# AnalogEx_1RedLedFadeInFadeOutUSB.net
KiCad netlist of a schematic drawn in EAGLE
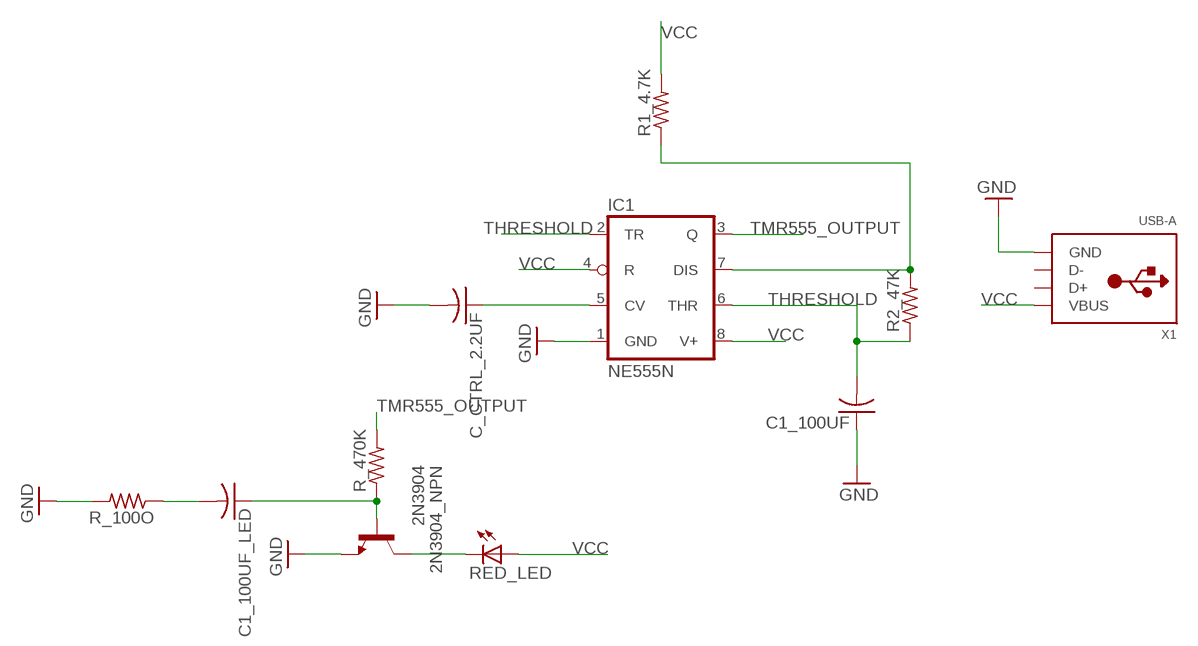
[diagram p0: schematic, sheet 1]

(export (version "E")
  (design (tool "Eeschema 10.0.6"))
  (components
    (comp (ref "2N3904_NPN")
      (value "2N3904")
      (footprint "eagle-import:TO92")
      (libsource (lib "eagle-import") (part "2N3904"))
    )
    (comp (ref "C1_100UF")
      (value "C-US025-030X050")
      (footprint "eagle-import:C025-030X050")
      (libsource (lib "eagle-import") (part "C-US025-030X050"))
    )
    (comp (ref "C1_100UF_LED")
      (value "C-US025-030X050")
      (footprint "eagle-import:C025-030X050")
      (libsource (lib "eagle-import") (part "C-US025-030X050"))
    )
    (comp (ref "C_CTRL_2.2UF")
      (value "C-US025-030X050")
      (footprint "eagle-import:C025-030X050")
      (libsource (lib "eagle-import") (part "C-US025-030X050"))
    )
    (comp (ref "IC1")
      (value "NE555N")
      (footprint "eagle-import:DIL08")
      (libsource (lib "eagle-import") (part "555NNE"))
    )
    (comp (ref "R1_4.7K")
      (value "R-US_0207/10")
      (footprint "eagle-import:0207_10")
      (libsource (lib "eagle-import") (part "R-US_0207/10"))
    )
    (comp (ref "R2_47K")
      (value "R-US_0207/10")
      (footprint "eagle-import:0207_10")
      (libsource (lib "eagle-import") (part "R-US_0207/10"))
    )
    (comp (ref "RED_LED")
      (value "LED5MM")
      (footprint "eagle-import:LED5MM")
      (libsource (lib "eagle-import") (part "LED5MM"))
    )
    (comp (ref "R_100O")
      (value "R-US_0207/10")
      (footprint "eagle-import:0207_10")
      (libsource (lib "eagle-import") (part "R-US_0207/10"))
    )
    (comp (ref "R_470K")
      (value "R-US_0207/10")
      (footprint "eagle-import:0207_10")
      (libsource (lib "eagle-import") (part "R-US_0207/10"))
    )
    (comp (ref "X1")
      (value "USB-A")
      (footprint "eagle-import:MOLEX_480371000")
      (libsource (lib "eagle-import") (part "USB-A"))
    )
  )
  (nets
    (net (code "1") (name "/THRESHOLD") (class "Default")
      (node (ref "C1_100UF") (pin "2") (pinfunction "2_2") (pintype "passive"))
      (node (ref "IC1") (pin "2") (pinfunction "TR_2") (pintype "input"))
      (node (ref "IC1") (pin "6") (pinfunction "THR_6") (pintype "input"))
      (node (ref "R2_47K") (pin "1") (pinfunction "1_1") (pintype "passive"))
    )
    (net (code "2") (name "/TMR555_OUTPUT") (class "Default")
      (node (ref "IC1") (pin "3") (pinfunction "Q_3") (pintype "output"))
      (node (ref "R_470K") (pin "2") (pinfunction "2_2") (pintype "passive"))
    )
    (net (code "3") (name "/VCC") (class "Default")
      (node (ref "IC1") (pin "4") (pinfunction "R_4") (pintype "input"))
      (node (ref "IC1") (pin "8") (pinfunction "V+_8") (pintype "power_in"))
      (node (ref "R1_4.7K") (pin "2") (pinfunction "2_2") (pintype "passive"))
      (node (ref "RED_LED") (pin "A") (pinfunction "A_A") (pintype "passive"))
      (node (ref "X1") (pin "1") (pinfunction "VBUS_1") (pintype "power_in"))
    )
    (net (code "4") (name "GND") (class "Default")
      (node (ref "2N3904_NPN") (pin "3") (pinfunction "E_3") (pintype "passive"))
      (node (ref "C1_100UF") (pin "1") (pinfunction "1_1") (pintype "passive"))
      (node (ref "C_CTRL_2.2UF") (pin "2") (pinfunction "2_2") (pintype "passive"))
      (node (ref "IC1") (pin "1") (pinfunction "GND_1") (pintype "power_in"))
      (node (ref "R_100O") (pin "2") (pinfunction "2_2") (pintype "passive"))
      (node (ref "X1") (pin "4") (pinfunction "GND_4") (pintype "power_in"))
    )
    (net (code "5") (name "Net-(2N3904_NPN-B)") (class "Default")
      (node (ref "2N3904_NPN") (pin "2") (pinfunction "B_2") (pintype "passive"))
      (node (ref "C1_100UF_LED") (pin "1") (pinfunction "1_1") (pintype "passive"))
      (node (ref "R_470K") (pin "1") (pinfunction "1_1") (pintype "passive"))
    )
    (net (code "6") (name "Net-(2N3904_NPN-C)") (class "Default")
      (node (ref "2N3904_NPN") (pin "1") (pinfunction "C_1") (pintype "passive"))
      (node (ref "RED_LED") (pin "K") (pinfunction "C_K") (pintype "passive"))
    )
    (net (code "7") (name "Net-(C1_100UF_LED-Pad2)") (class "Default")
      (node (ref "C1_100UF_LED") (pin "2") (pinfunction "2_2") (pintype "passive"))
      (node (ref "R_100O") (pin "1") (pinfunction "1_1") (pintype "passive"))
    )
    (net (code "8") (name "Net-(IC1-CV)") (class "Default")
      (node (ref "C_CTRL_2.2UF") (pin "1") (pinfunction "1_1") (pintype "passive"))
      (node (ref "IC1") (pin "5") (pinfunction "CV_5") (pintype "input"))
    )
    (net (code "9") (name "Net-(IC1-DIS)") (class "Default")
      (node (ref "IC1") (pin "7") (pinfunction "DIS_7") (pintype "input"))
      (node (ref "R1_4.7K") (pin "1") (pinfunction "1_1") (pintype "passive"))
      (node (ref "R2_47K") (pin "2") (pinfunction "2_2") (pintype "passive"))
    )
    (net (code "10") (name "unconnected-(X1-D+-Pad3)") (class "Default")
      (node (ref "X1") (pin "3") (pinfunction "D+_3") (pintype "bidirectional"))
    )
    (net (code "11") (name "unconnected-(X1-D--Pad2)") (class "Default")
      (node (ref "X1") (pin "2") (pinfunction "D-_2") (pintype "bidirectional"))
    )
  )
)
